# Sheet1.net
KiCad netlist of a schematic drawn in Altium Designer
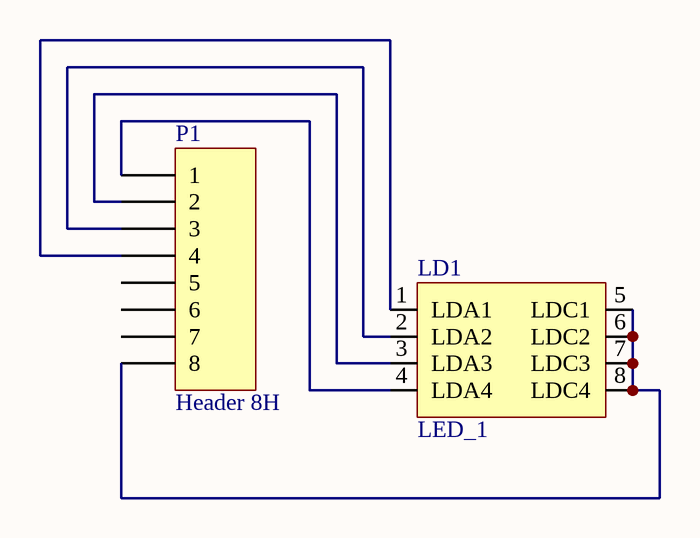
[diagram p0: Sheet1.SchDoc]

(export (version "E")
  (design (tool "Eeschema 10.0.6"))
  (components
    (comp (ref "LD1")
      (value "LED_1")
      (footprint "PcbLib:LED_1")
      (libsource (lib "Schlib_IDQ") (part "LED_1"))
    )
    (comp (ref "P1")
      (value "Header 8H")
      (footprint "HDR1X8H")
      (description "Header, 8-Pin, Right Angle")
      (fields (field (name "PUBLISHER") "Altium Limited"))
      (libsource (lib "Miscellaneous Connectors") (part "Header 8H"))
    )
  )
  (nets
    (net (code "1") (name "Net-(LD1-LDA1)") (class "Default")
      (node (ref "LD1") (pin "1") (pinfunction "LDA1_1") (pintype "passive"))
      (node (ref "P1") (pin "4") (pinfunction "4_4") (pintype "passive"))
    )
    (net (code "2") (name "Net-(LD1-LDA2)") (class "Default")
      (node (ref "LD1") (pin "2") (pinfunction "LDA2_2") (pintype "passive"))
      (node (ref "P1") (pin "3") (pinfunction "3_3") (pintype "passive"))
    )
    (net (code "3") (name "Net-(LD1-LDA3)") (class "Default")
      (node (ref "LD1") (pin "3") (pinfunction "LDA3_3") (pintype "passive"))
      (node (ref "P1") (pin "2") (pinfunction "2_2") (pintype "passive"))
    )
    (net (code "4") (name "Net-(LD1-LDA4)") (class "Default")
      (node (ref "LD1") (pin "4") (pinfunction "LDA4_4") (pintype "passive"))
      (node (ref "P1") (pin "1") (pinfunction "1_1") (pintype "passive"))
    )
    (net (code "5") (name "Net-(LD1-LDC2)") (class "Default")
      (node (ref "LD1") (pin "5") (pinfunction "LDС1_5") (pintype "passive"))
      (node (ref "LD1") (pin "6") (pinfunction "LDC2_6") (pintype "passive"))
      (node (ref "LD1") (pin "7") (pinfunction "LDC3_7") (pintype "passive"))
      (node (ref "LD1") (pin "8") (pinfunction "LDC4_8") (pintype "passive"))
      (node (ref "P1") (pin "8") (pinfunction "8_8") (pintype "passive"))
    )
    (net (code "6") (name "unconnected-(P1-Pad5)") (class "Default")
      (node (ref "P1") (pin "5") (pinfunction "5_5") (pintype "passive"))
    )
    (net (code "7") (name "unconnected-(P1-Pad6)") (class "Default")
      (node (ref "P1") (pin "6") (pinfunction "6_6") (pintype "passive"))
    )
    (net (code "8") (name "unconnected-(P1-Pad7)") (class "Default")
      (node (ref "P1") (pin "7") (pinfunction "7_7") (pintype "passive"))
    )
  )
)
